# LightLab.net
KiCad netlist of a schematic drawn in EAGLE
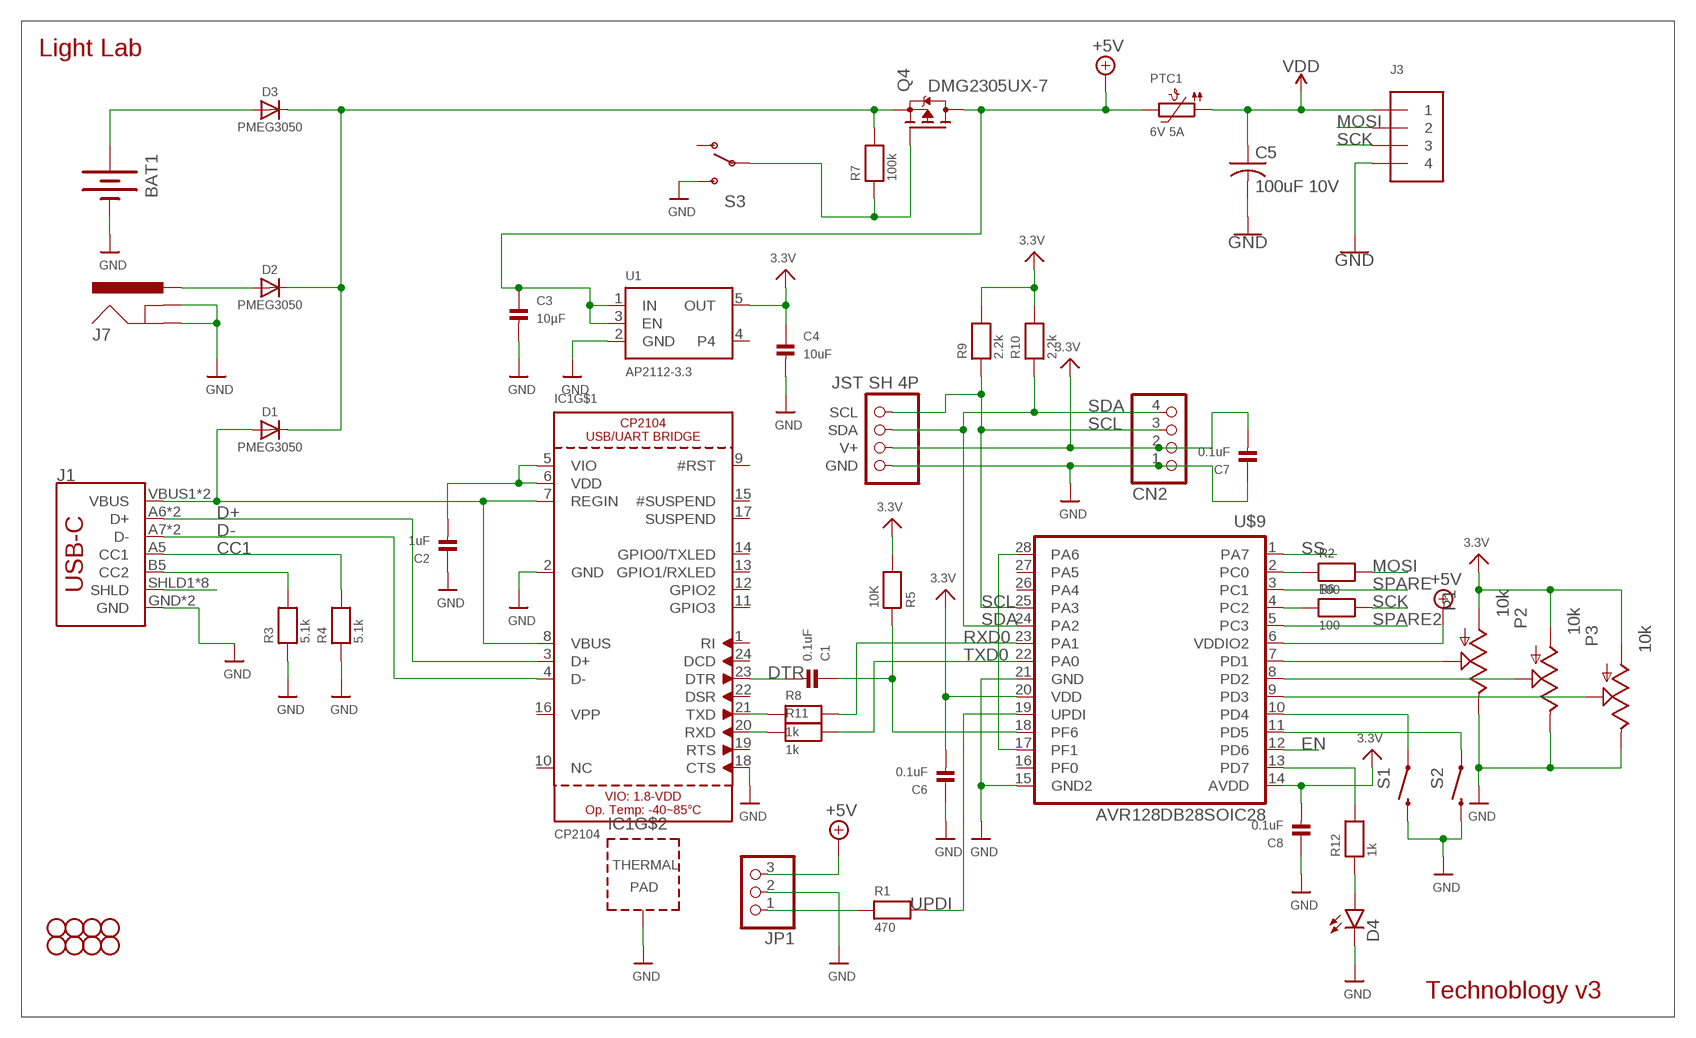
[diagram p0: schematic, sheet 1]

(export (version "E")
  (design (tool "Eeschema 10.0.6"))
  (components
    (comp (ref "BAT1")
      (value "BATTERY18650")
      (footprint "eagle-import:BATTERY_18650-HOLDER")
      (libsource (lib "eagle-import") (part "BATTERY18650"))
    )
    (comp (ref "C1")
      (value "0.1uF")
      (footprint "eagle-import:_0805MP")
      (libsource (lib "eagle-import") (part "CAP_CERAMIC_0805MP"))
    )
    (comp (ref "C2")
      (value "1uF")
      (footprint "eagle-import:_0805MP")
      (libsource (lib "eagle-import") (part "CAP_CERAMIC_0805MP"))
    )
    (comp (ref "C3")
      (value "10µF")
      (footprint "eagle-import:_0805MP")
      (libsource (lib "eagle-import") (part "CAP_CERAMIC_0805MP"))
    )
    (comp (ref "C4")
      (value "10uF")
      (footprint "eagle-import:_0805MP")
      (libsource (lib "eagle-import") (part "CAP_CERAMIC_0805MP"))
    )
    (comp (ref "C5")
      (value "100uF 10V")
      (footprint "eagle-import:C1210")
      (libsource (lib "eagle-import") (part "C-USC1210"))
    )
    (comp (ref "C6")
      (value "0.1uF")
      (footprint "eagle-import:_0805MP")
      (libsource (lib "eagle-import") (part "CAP_CERAMIC_0805MP"))
    )
    (comp (ref "C7")
      (value "0.1uF")
      (footprint "eagle-import:_0805MP")
      (libsource (lib "eagle-import") (part "CAP_CERAMIC_0805MP"))
    )
    (comp (ref "C8")
      (value "0.1uF")
      (footprint "eagle-import:_0805MP")
      (libsource (lib "eagle-import") (part "CAP_CERAMIC_0805MP"))
    )
    (comp (ref "CN2")
      (value "HEADER-1X4ROUND")
      (footprint "eagle-import:1X04_ROUND")
      (libsource (lib "eagle-import") (part "HEADER-1X4ROUND"))
    )
    (comp (ref "CONN1")
      (value "JST SH 4P")
      (footprint "eagle-import:JST_SH4")
      (libsource (lib "eagle-import") (part "STEMMA_I2C_QT"))
    )
    (comp (ref "D1")
      (value "PMEG3050")
      (footprint "eagle-import:SOD-128")
      (libsource (lib "eagle-import") (part "DIODE_SOD128"))
    )
    (comp (ref "D2")
      (value "PMEG3050")
      (footprint "eagle-import:SOD-128")
      (libsource (lib "eagle-import") (part "DIODE_SOD128"))
    )
    (comp (ref "D3")
      (value "PMEG3050")
      (footprint "eagle-import:SOD-128")
      (libsource (lib "eagle-import") (part "DIODE_SOD128"))
    )
    (comp (ref "D4")
      (value "LED1206-BOTTOM")
      (footprint "eagle-import:LED-1206-BOTTOM")
      (libsource (lib "eagle-import") (part "LED1206-BOTTOM"))
    )
    (comp (ref "IC1")
      (value "CP2104")
      (footprint "eagle-import:QFN24_4MM_SMSC")
      (libsource (lib "eagle-import") (part "CP2104"))
    )
    (comp (ref "J1")
      (value "USB_C2-LAYER")
      (footprint "eagle-import:USB-C-16P")
      (libsource (lib "eagle-import") (part "USB_C2-LAYER"))
    )
    (comp (ref "J3")
      (value "TERMBLOCK_1X4")
      (footprint "eagle-import:TERMBLOCK_1X3-3.5MM")
      (libsource (lib "eagle-import") (part "TERMBLOCK_1X4"))
    )
    (comp (ref "J7")
      (value "5.5x2.1mm Barrel")
      (footprint "eagle-import:POWER_JACK_SMD")
      (libsource (lib "eagle-import") (part "POWER_JACKSMD"))
    )
    (comp (ref "JP1")
      (value "HEADER-1X3ROUND")
      (footprint "eagle-import:1X03_ROUND")
      (libsource (lib "eagle-import") (part "HEADER-1X3ROUND"))
    )
    (comp (ref "JP8")
      (value "STAND-OFF")
      (footprint "eagle-import:STAND-OFF")
      (libsource (lib "eagle-import") (part "STAND-OFF"))
    )
    (comp (ref "JP9")
      (value "STAND-OFF")
      (footprint "eagle-import:STAND-OFF")
      (libsource (lib "eagle-import") (part "STAND-OFF"))
    )
    (comp (ref "JP10")
      (value "STAND-OFF")
      (footprint "eagle-import:STAND-OFF")
      (libsource (lib "eagle-import") (part "STAND-OFF"))
    )
    (comp (ref "JP11")
      (value "STAND-OFF")
      (footprint "eagle-import:STAND-OFF")
      (libsource (lib "eagle-import") (part "STAND-OFF"))
    )
    (comp (ref "JP12")
      (value "STAND-OFF")
      (footprint "eagle-import:STAND-OFF")
      (libsource (lib "eagle-import") (part "STAND-OFF"))
    )
    (comp (ref "JP13")
      (value "STAND-OFF")
      (footprint "eagle-import:STAND-OFF")
      (libsource (lib "eagle-import") (part "STAND-OFF"))
    )
    (comp (ref "JP14")
      (value "STAND-OFF")
      (footprint "eagle-import:STAND-OFF")
      (libsource (lib "eagle-import") (part "STAND-OFF"))
    )
    (comp (ref "JP15")
      (value "STAND-OFF")
      (footprint "eagle-import:STAND-OFF")
      (libsource (lib "eagle-import") (part "STAND-OFF"))
    )
    (comp (ref "P1")
      (value "10k")
      (footprint "eagle-import:ALPS_POT")
      (libsource (lib "eagle-import") (part "POT"))
    )
    (comp (ref "P2")
      (value "10k")
      (footprint "eagle-import:ALPS_POT")
      (libsource (lib "eagle-import") (part "POT"))
    )
    (comp (ref "P3")
      (value "10k")
      (footprint "eagle-import:ALPS_POT")
      (libsource (lib "eagle-import") (part "POT"))
    )
    (comp (ref "PTC1")
      (value "6V 5A")
      (footprint "eagle-import:PTC1210")
      (libsource (lib "eagle-import") (part "PTC1210"))
    )
    (comp (ref "Q4")
      (value "DMG2305UX-7")
      (footprint "eagle-import:SOT23-WIDE")
      (libsource (lib "eagle-import") (part "MOSFET-PWIDE"))
    )
    (comp (ref "R1")
      (value "470")
      (footprint "eagle-import:_0805MP")
      (libsource (lib "eagle-import") (part "RESISTOR_0805MP"))
    )
    (comp (ref "R2")
      (value "100")
      (footprint "eagle-import:_0805MP")
      (libsource (lib "eagle-import") (part "RESISTOR_0805MP"))
    )
    (comp (ref "R3")
      (value "5.1k")
      (footprint "eagle-import:_0805MP")
      (libsource (lib "eagle-import") (part "RESISTOR_0805MP"))
    )
    (comp (ref "R4")
      (value "5.1k")
      (footprint "eagle-import:_0805MP")
      (libsource (lib "eagle-import") (part "RESISTOR_0805MP"))
    )
    (comp (ref "R5")
      (value "10K")
      (footprint "eagle-import:_0805MP")
      (libsource (lib "eagle-import") (part "RESISTOR_0805MP"))
    )
    (comp (ref "R6")
      (value "100")
      (footprint "eagle-import:_0805MP")
      (libsource (lib "eagle-import") (part "RESISTOR_0805MP"))
    )
    (comp (ref "R7")
      (value "100k")
      (footprint "eagle-import:_0805MP")
      (libsource (lib "eagle-import") (part "RESISTOR_0805MP"))
    )
    (comp (ref "R8")
      (value "1k")
      (footprint "eagle-import:_0805MP")
      (libsource (lib "eagle-import") (part "RESISTOR_0805MP"))
    )
    (comp (ref "R9")
      (value "2.2k")
      (footprint "eagle-import:_0805MP")
      (libsource (lib "eagle-import") (part "RESISTOR_0805MP"))
    )
    (comp (ref "R10")
      (value "2.2k")
      (footprint "eagle-import:_0805MP")
      (libsource (lib "eagle-import") (part "RESISTOR_0805MP"))
    )
    (comp (ref "R11")
      (value "1k")
      (footprint "eagle-import:_0805MP")
      (libsource (lib "eagle-import") (part "RESISTOR_0805MP"))
    )
    (comp (ref "R12")
      (value "1k")
      (footprint "eagle-import:_0805MP")
      (libsource (lib "eagle-import") (part "RESISTOR_0805MP"))
    )
    (comp (ref "S1")
      (value "SWITCH-MOMENTARY-2PTH")
      (footprint "eagle-import:TACTILE-PTH")
      (libsource (lib "eagle-import") (part "SWITCH-MOMENTARY-2PTH"))
    )
    (comp (ref "S2")
      (value "SWITCH-MOMENTARY-2PTH")
      (footprint "eagle-import:TACTILE-PTH")
      (libsource (lib "eagle-import") (part "SWITCH-MOMENTARY-2PTH"))
    )
    (comp (ref "S3")
      (value "SWITCH-SPDTKIT")
      (footprint "eagle-import:SWITCH-SPDT_KIT")
      (libsource (lib "eagle-import") (part "SWITCH-SPDTKIT"))
    )
    (comp (ref "U$9")
      (value "AVR128DB28SOIC28")
      (footprint "eagle-import:SO-28W")
      (libsource (lib "eagle-import") (part "AVR128DB28SOIC28"))
    )
    (comp (ref "U1")
      (value "AP2112-3.3")
      (footprint "eagle-import:SOT23-5")
      (libsource (lib "eagle-import") (part "VREG_SOT23-5"))
    )
  )
  (nets
    (net (code "1") (name "+5V") (class "Default")
      (node (ref "C3") (pin "1") (pinfunction "P$1_1") (pintype "passive"))
      (node (ref "JP1") (pin "3") (pinfunction "3_3") (pintype "passive"))
      (node (ref "PTC1") (pin "P$2") (pinfunction "2_P$2") (pintype "passive"))
      (node (ref "Q4") (pin "3") (pinfunction "D_3") (pintype "passive"))
      (node (ref "U$9") (pin "6") (pinfunction "VDDIO2_6") (pintype "bidirectional"))
      (node (ref "U1") (pin "1") (pinfunction "IN_1") (pintype "power_in"))
      (node (ref "U1") (pin "3") (pinfunction "EN_3") (pintype "input"))
    )
    (net (code "2") (name "/CC1") (class "Default")
      (node (ref "J1") (pin "A5") (pinfunction "CC1_A5") (pintype "bidirectional"))
      (node (ref "R4") (pin "2") (pinfunction "2_2") (pintype "passive"))
    )
    (net (code "3") (name "/D+") (class "Default")
      (node (ref "IC1") (pin "3") (pinfunction "D+_3") (pintype "bidirectional"))
      (node (ref "J1") (pin "A6") (pinfunction "D+_A6") (pintype "bidirectional"))
      (node (ref "J1") (pin "B6") (pinfunction "D+_B6") (pintype "bidirectional"))
    )
    (net (code "4") (name "/D-") (class "Default")
      (node (ref "IC1") (pin "4") (pinfunction "D-_4") (pintype "bidirectional"))
      (node (ref "J1") (pin "A7") (pinfunction "D-_A7") (pintype "bidirectional"))
      (node (ref "J1") (pin "B7") (pinfunction "D-_B7") (pintype "bidirectional"))
    )
    (net (code "5") (name "/DTR") (class "Default")
      (node (ref "C1") (pin "2") (pinfunction "P$2_2") (pintype "passive"))
      (node (ref "IC1") (pin "23") (pinfunction "DTR_23") (pintype "output"))
    )
    (net (code "6") (name "/EN") (class "Default")
      (node (ref "U$9") (pin "12") (pinfunction "PD6_12") (pintype "bidirectional"))
    )
    (net (code "7") (name "/MOSI") (class "Default")
      (node (ref "J3") (pin "2") (pinfunction "2_2") (pintype "passive"))
      (node (ref "R2") (pin "2") (pinfunction "2_2") (pintype "passive"))
    )
    (net (code "8") (name "/RXD0") (class "Default")
      (node (ref "R8") (pin "2") (pinfunction "2_2") (pintype "passive"))
      (node (ref "U$9") (pin "23") (pinfunction "PA1_23") (pintype "bidirectional"))
    )
    (net (code "9") (name "/SCK") (class "Default")
      (node (ref "J3") (pin "3") (pinfunction "3_3") (pintype "passive"))
      (node (ref "R6") (pin "2") (pinfunction "2_2") (pintype "passive"))
    )
    (net (code "10") (name "/SCL") (class "Default")
      (node (ref "CN2") (pin "3") (pinfunction "3_3") (pintype "passive"))
      (node (ref "CONN1") (pin "4") (pinfunction "SCL_4") (pintype "passive"))
      (node (ref "R9") (pin "1") (pinfunction "1_1") (pintype "passive"))
      (node (ref "U$9") (pin "25") (pinfunction "PA3_25") (pintype "bidirectional"))
    )
    (net (code "11") (name "/SDA") (class "Default")
      (node (ref "CN2") (pin "4") (pinfunction "4_4") (pintype "passive"))
      (node (ref "CONN1") (pin "3") (pinfunction "SDA_3") (pintype "passive"))
      (node (ref "R10") (pin "1") (pinfunction "1_1") (pintype "passive"))
      (node (ref "U$9") (pin "24") (pinfunction "PA2_24") (pintype "bidirectional"))
    )
    (net (code "12") (name "/SPARE") (class "Default")
      (node (ref "U$9") (pin "3") (pinfunction "PC1_3") (pintype "bidirectional"))
    )
    (net (code "13") (name "/SPARE2") (class "Default")
      (node (ref "U$9") (pin "5") (pinfunction "PC3_5") (pintype "bidirectional"))
    )
    (net (code "14") (name "/SS") (class "Default")
      (node (ref "U$9") (pin "1") (pinfunction "PA7_1") (pintype "bidirectional"))
    )
    (net (code "15") (name "/TXD0") (class "Default")
      (node (ref "R11") (pin "2") (pinfunction "2_2") (pintype "passive"))
      (node (ref "U$9") (pin "22") (pinfunction "PA0_22") (pintype "bidirectional"))
    )
    (net (code "16") (name "/UPDI") (class "Default")
      (node (ref "R1") (pin "2") (pinfunction "2_2") (pintype "passive"))
      (node (ref "U$9") (pin "19") (pinfunction "UPDI_19") (pintype "power_in"))
    )
    (net (code "17") (name "3.3V") (class "Default")
      (node (ref "C4") (pin "1") (pinfunction "P$1_1") (pintype "passive"))
      (node (ref "C6") (pin "2") (pinfunction "P$2_2") (pintype "passive"))
      (node (ref "C7") (pin "2") (pinfunction "P$2_2") (pintype "passive"))
      (node (ref "C8") (pin "2") (pinfunction "P$2_2") (pintype "passive"))
      (node (ref "CN2") (pin "2") (pinfunction "2_2") (pintype "passive"))
      (node (ref "CONN1") (pin "2") (pinfunction "V+_2") (pintype "passive"))
      (node (ref "P1") (pin "P$3") (pinfunction "A_P$3") (pintype "passive"))
      (node (ref "P2") (pin "P$3") (pinfunction "A_P$3") (pintype "passive"))
      (node (ref "P3") (pin "P$3") (pinfunction "A_P$3") (pintype "passive"))
      (node (ref "R10") (pin "2") (pinfunction "2_2") (pintype "passive"))
      (node (ref "R5") (pin "2") (pinfunction "2_2") (pintype "passive"))
      (node (ref "R9") (pin "2") (pinfunction "2_2") (pintype "passive"))
      (node (ref "U$9") (pin "14") (pinfunction "AVDD_14") (pintype "bidirectional"))
      (node (ref "U$9") (pin "20") (pinfunction "VDD_20") (pintype "power_in"))
      (node (ref "U1") (pin "5") (pinfunction "OUT_5") (pintype "power_in"))
    )
    (net (code "18") (name "GND") (class "Default")
      (node (ref "BAT1") (pin "GND@1") (pinfunction "-_GND@1") (pintype "power_in"))
      (node (ref "C2") (pin "1") (pinfunction "P$1_1") (pintype "passive"))
      (node (ref "C3") (pin "2") (pinfunction "P$2_2") (pintype "passive"))
      (node (ref "C4") (pin "2") (pinfunction "P$2_2") (pintype "passive"))
      (node (ref "C5") (pin "2") (pinfunction "2_2") (pintype "passive"))
      (node (ref "C6") (pin "1") (pinfunction "P$1_1") (pintype "passive"))
      (node (ref "C7") (pin "1") (pinfunction "P$1_1") (pintype "passive"))
      (node (ref "C8") (pin "1") (pinfunction "P$1_1") (pintype "passive"))
      (node (ref "CN2") (pin "1") (pinfunction "1_1") (pintype "passive"))
      (node (ref "CONN1") (pin "1") (pinfunction "GND_1") (pintype "passive"))
      (node (ref "D4") (pin "C") (pinfunction "C_C") (pintype "passive"))
      (node (ref "IC1") (pin "18") (pinfunction "CTS_18") (pintype "input"))
      (node (ref "IC1") (pin "2") (pinfunction "GND_2") (pintype "power_in"))
      (node (ref "IC1") (pin "THERM") (pinfunction "TP_THERM") (pintype "power_in"))
      (node (ref "J1") (pin "GND") (pinfunction "GND_GND") (pintype "bidirectional"))
      (node (ref "J1") (pin "GND2") (pinfunction "GND_GND2") (pintype "bidirectional"))
      (node (ref "J3") (pin "4") (pinfunction "4_4") (pintype "passive"))
      (node (ref "J7") (pin "GND") (pinfunction "GNDBREAK_GND") (pintype "bidirectional"))
      (node (ref "J7") (pin "P$4") (pinfunction "GND_P$4") (pintype "bidirectional"))
      (node (ref "JP1") (pin "2") (pinfunction "2_2") (pintype "passive"))
      (node (ref "P1") (pin "P$1") (pinfunction "E_P$1") (pintype "passive"))
      (node (ref "P2") (pin "P$1") (pinfunction "E_P$1") (pintype "passive"))
      (node (ref "P3") (pin "P$1") (pinfunction "E_P$1") (pintype "passive"))
      (node (ref "R3") (pin "1") (pinfunction "1_1") (pintype "passive"))
      (node (ref "R4") (pin "1") (pinfunction "1_1") (pintype "passive"))
      (node (ref "S1") (pin "3") (pinfunction "2_3") (pintype "passive"))
      (node (ref "S2") (pin "3") (pinfunction "2_3") (pintype "passive"))
      (node (ref "S3") (pin "3") (pinfunction "S_3") (pintype "passive"))
      (node (ref "U$9") (pin "15") (pinfunction "GND2_15") (pintype "bidirectional"))
      (node (ref "U$9") (pin "21") (pinfunction "GND_21") (pintype "bidirectional"))
      (node (ref "U1") (pin "2") (pinfunction "GND_2") (pintype "power_in"))
    )
    (net (code "19") (name "Net-(BAT1-+)") (class "Default")
      (node (ref "BAT1") (pin "PWR@1") (pinfunction "+_PWR@1") (pintype "power_in"))
      (node (ref "D3") (pin "A") (pinfunction "A_A") (pintype "passive"))
    )
    (net (code "20") (name "Net-(C1-P$1)") (class "Default")
      (node (ref "C1") (pin "1") (pinfunction "P$1_1") (pintype "passive"))
      (node (ref "R5") (pin "1") (pinfunction "1_1") (pintype "passive"))
      (node (ref "U$9") (pin "18") (pinfunction "PF6_18") (pintype "input"))
    )
    (net (code "21") (name "Net-(C2-P$2)") (class "Default")
      (node (ref "C2") (pin "2") (pinfunction "P$2_2") (pintype "passive"))
      (node (ref "IC1") (pin "5") (pinfunction "VIO_5") (pintype "power_in"))
      (node (ref "IC1") (pin "6") (pinfunction "VDD_6") (pintype "power_in"))
    )
    (net (code "22") (name "Net-(D4-PadA)") (class "Default")
      (node (ref "D4") (pin "A") (pinfunction "A_A") (pintype "passive"))
      (node (ref "R12") (pin "1") (pinfunction "1_1") (pintype "passive"))
    )
    (net (code "23") (name "Net-(IC1A-REGIN)") (class "Default")
      (node (ref "D1") (pin "A") (pinfunction "A_A") (pintype "passive"))
      (node (ref "IC1") (pin "7") (pinfunction "REGIN_7") (pintype "power_in"))
      (node (ref "IC1") (pin "8") (pinfunction "VBUS_8") (pintype "power_in"))
      (node (ref "J1") (pin "VBUS1") (pinfunction "VBUS_VBUS1") (pintype "bidirectional"))
      (node (ref "J1") (pin "VBUS2") (pinfunction "VBUS_VBUS2") (pintype "bidirectional"))
    )
    (net (code "24") (name "Net-(IC1A-RXD)") (class "Default")
      (node (ref "IC1") (pin "20") (pinfunction "RXD_20") (pintype "input"))
      (node (ref "R11") (pin "1") (pinfunction "1_1") (pintype "passive"))
    )
    (net (code "25") (name "Net-(IC1A-TXD)") (class "Default")
      (node (ref "IC1") (pin "21") (pinfunction "TXD_21") (pintype "output"))
      (node (ref "R8") (pin "1") (pinfunction "1_1") (pintype "passive"))
    )
    (net (code "26") (name "Net-(J1-CC2)") (class "Default")
      (node (ref "J1") (pin "B5") (pinfunction "CC2_B5") (pintype "bidirectional"))
      (node (ref "R3") (pin "2") (pinfunction "2_2") (pintype "passive"))
    )
    (net (code "27") (name "Net-(J1-SHLD-PadSHLD1)") (class "Default")
      (node (ref "J1") (pin "SHLD1") (pinfunction "SHLD_SHLD1") (pintype "bidirectional"))
      (node (ref "J1") (pin "SHLD2") (pinfunction "SHLD_SHLD2") (pintype "bidirectional"))
      (node (ref "J1") (pin "SHLD3") (pinfunction "SHLD_SHLD3") (pintype "bidirectional"))
      (node (ref "J1") (pin "SHLD4") (pinfunction "SHLD_SHLD4") (pintype "bidirectional"))
      (node (ref "J1") (pin "SHLD5") (pinfunction "SHLD_SHLD5") (pintype "bidirectional"))
      (node (ref "J1") (pin "SHLD6") (pinfunction "SHLD_SHLD6") (pintype "bidirectional"))
      (node (ref "J1") (pin "SHLD7") (pinfunction "SHLD_SHLD7") (pintype "bidirectional"))
      (node (ref "J1") (pin "SHLD8") (pinfunction "SHLD_SHLD8") (pintype "bidirectional"))
    )
    (net (code "28") (name "Net-(J7-PWR)") (class "Default")
      (node (ref "D2") (pin "A") (pinfunction "A_A") (pintype "passive"))
      (node (ref "J7") (pin "VIN0") (pinfunction "PWR_VIN0") (pintype "bidirectional"))
    )
    (net (code "29") (name "Net-(JP1-Pad1)") (class "Default")
      (node (ref "JP1") (pin "1") (pinfunction "1_1") (pintype "passive"))
      (node (ref "R1") (pin "1") (pinfunction "1_1") (pintype "passive"))
    )
    (net (code "30") (name "Net-(P1-S)") (class "Default")
      (node (ref "P1") (pin "P$2") (pinfunction "S_P$2") (pintype "passive"))
      (node (ref "U$9") (pin "7") (pinfunction "PD1_7") (pintype "bidirectional"))
    )
    (net (code "31") (name "Net-(P2-S)") (class "Default")
      (node (ref "P2") (pin "P$2") (pinfunction "S_P$2") (pintype "passive"))
      (node (ref "U$9") (pin "8") (pinfunction "PD2_8") (pintype "power_in"))
    )
    (net (code "32") (name "Net-(P3-S)") (class "Default")
      (node (ref "P3") (pin "P$2") (pinfunction "S_P$2") (pintype "passive"))
      (node (ref "U$9") (pin "9") (pinfunction "PD3_9") (pintype "bidirectional"))
    )
    (net (code "33") (name "Net-(Q4-G)") (class "Default")
      (node (ref "Q4") (pin "1") (pinfunction "G_1") (pintype "passive"))
      (node (ref "R7") (pin "1") (pinfunction "1_1") (pintype "passive"))
      (node (ref "S3") (pin "2") (pinfunction "P_2") (pintype "passive"))
    )
    (net (code "34") (name "Net-(Q4-S)") (class "Default")
      (node (ref "D1") (pin "C") (pinfunction "C_C") (pintype "passive"))
      (node (ref "D2") (pin "C") (pinfunction "C_C") (pintype "passive"))
      (node (ref "D3") (pin "C") (pinfunction "C_C") (pintype "passive"))
      (node (ref "Q4") (pin "2") (pinfunction "S_2") (pintype "passive"))
      (node (ref "R7") (pin "2") (pinfunction "2_2") (pintype "passive"))
    )
    (net (code "35") (name "Net-(U$9-PA6)") (class "Default")
      (node (ref "U$9") (pin "17") (pinfunction "PF1_17") (pintype "bidirectional"))
      (node (ref "U$9") (pin "28") (pinfunction "PA6_28") (pintype "bidirectional"))
    )
    (net (code "36") (name "Net-(U$9-PC0)") (class "Default")
      (node (ref "R2") (pin "1") (pinfunction "1_1") (pintype "passive"))
      (node (ref "U$9") (pin "2") (pinfunction "PC0_2") (pintype "bidirectional"))
    )
    (net (code "37") (name "Net-(U$9-PC2)") (class "Default")
      (node (ref "R6") (pin "1") (pinfunction "1_1") (pintype "passive"))
      (node (ref "U$9") (pin "4") (pinfunction "PC2_4") (pintype "bidirectional"))
    )
    (net (code "38") (name "Net-(U$9-PD4)") (class "Default")
      (node (ref "S1") (pin "1") (pinfunction "1_1") (pintype "passive"))
      (node (ref "U$9") (pin "10") (pinfunction "PD4_10") (pintype "bidirectional"))
    )
    (net (code "39") (name "Net-(U$9-PD5)") (class "Default")
      (node (ref "S2") (pin "1") (pinfunction "1_1") (pintype "passive"))
      (node (ref "U$9") (pin "11") (pinfunction "PD5_11") (pintype "bidirectional"))
    )
    (net (code "40") (name "Net-(U$9-PD7)") (class "Default")
      (node (ref "R12") (pin "2") (pinfunction "2_2") (pintype "passive"))
      (node (ref "U$9") (pin "13") (pinfunction "PD7_13") (pintype "bidirectional"))
    )
    (net (code "41") (name "VDD") (class "Default")
      (node (ref "C5") (pin "1") (pinfunction "1_1") (pintype "passive"))
      (node (ref "J3") (pin "1") (pinfunction "1_1") (pintype "passive"))
      (node (ref "PTC1") (pin "P$1") (pinfunction "1_P$1") (pintype "passive"))
    )
    (net (code "42") (name "unconnected-(IC1A-#RST-Pad9)") (class "Default")
      (node (ref "IC1") (pin "9") (pinfunction "#RST_9") (pintype "bidirectional"))
    )
    (net (code "43") (name "unconnected-(IC1A-#SUSPEND-Pad15)") (class "Default")
      (node (ref "IC1") (pin "15") (pinfunction "#SUSPEND_15") (pintype "output"))
    )
    (net (code "44") (name "unconnected-(IC1A-DCD-Pad24)") (class "Default")
      (node (ref "IC1") (pin "24") (pinfunction "DCD_24") (pintype "input"))
    )
    (net (code "45") (name "unconnected-(IC1A-DSR-Pad22)") (class "Default")
      (node (ref "IC1") (pin "22") (pinfunction "DSR_22") (pintype "input"))
    )
    (net (code "46") (name "unconnected-(IC1A-GPIO0{slash}TXLED-Pad14)") (class "Default")
      (node (ref "IC1") (pin "14") (pinfunction "GPIO0/TXLED_14") (pintype "bidirectional"))
    )
    (net (code "47") (name "unconnected-(IC1A-GPIO1{slash}RXLED-Pad13)") (class "Default")
      (node (ref "IC1") (pin "13") (pinfunction "GPIO1/RXLED_13") (pintype "bidirectional"))
    )
    (net (code "48") (name "unconnected-(IC1A-GPIO2-Pad12)") (class "Default")
      (node (ref "IC1") (pin "12") (pinfunction "GPIO2_12") (pintype "bidirectional"))
    )
    (net (code "49") (name "unconnected-(IC1A-GPIO3-Pad11)") (class "Default")
      (node (ref "IC1") (pin "11") (pinfunction "GPIO3_11") (pintype "bidirectional"))
    )
    (net (code "50") (name "unconnected-(IC1A-NC-Pad10)") (class "Default")
      (node (ref "IC1") (pin "10") (pinfunction "NC_10") (pintype "no_connect"))
    )
    (net (code "51") (name "unconnected-(IC1A-RI-Pad1)") (class "Default")
      (node (ref "IC1") (pin "1") (pinfunction "RI_1") (pintype "input"))
    )
    (net (code "52") (name "unconnected-(IC1A-RTS-Pad19)") (class "Default")
      (node (ref "IC1") (pin "19") (pinfunction "RTS_19") (pintype "output"))
    )
    (net (code "53") (name "unconnected-(IC1A-SUSPEND-Pad17)") (class "Default")
      (node (ref "IC1") (pin "17") (pinfunction "SUSPEND_17") (pintype "output"))
    )
    (net (code "54") (name "unconnected-(IC1A-VPP-Pad16)") (class "Default")
      (node (ref "IC1") (pin "16") (pinfunction "VPP_16") (pintype "bidirectional"))
    )
    (net (code "55") (name "unconnected-(S3-O-Pad1)") (class "Default")
      (node (ref "S3") (pin "1") (pinfunction "O_1") (pintype "passive"))
    )
    (net (code "56") (name "unconnected-(U$9-PA4-Pad26)") (class "Default")
      (node (ref "U$9") (pin "26") (pinfunction "PA4_26") (pintype "bidirectional"))
    )
    (net (code "57") (name "unconnected-(U$9-PA5-Pad27)") (class "Default")
      (node (ref "U$9") (pin "27") (pinfunction "PA5_27") (pintype "bidirectional"))
    )
    (net (code "58") (name "unconnected-(U$9-PF0-Pad16)") (class "Default")
      (node (ref "U$9") (pin "16") (pinfunction "PF0_16") (pintype "bidirectional"))
    )
    (net (code "59") (name "unconnected-(U1-P4-Pad4)") (class "Default")
      (node (ref "U1") (pin "4") (pinfunction "P4_4") (pintype "bidirectional"))
    )
  )
)
